# progshield.net
KiCad netlist of a schematic drawn in EAGLE
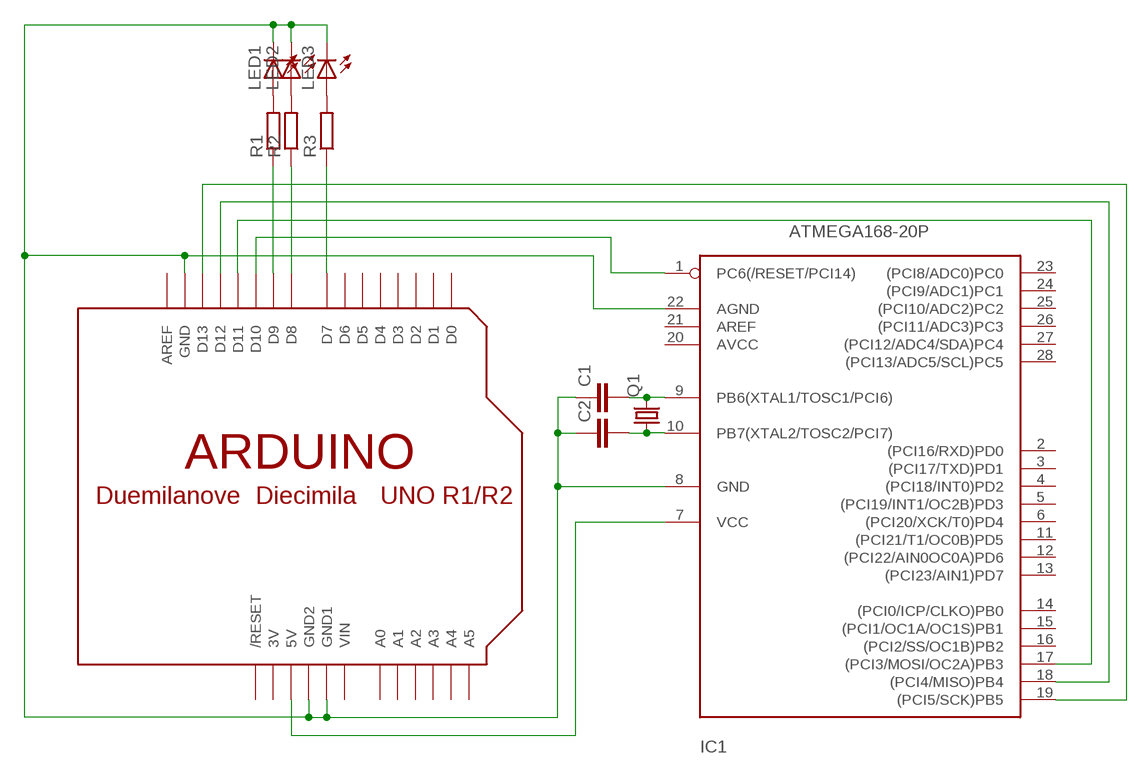
[diagram p0: schematic, sheet 1]

(export (version "E")
  (design (tool "Eeschema 10.0.6"))
  (components
    (comp (ref "C1")
      (value "C-EU025-030X050")
      (footprint "eagle-import:C025-030X050")
      (libsource (lib "eagle-import") (part "C-EU025-030X050"))
    )
    (comp (ref "C2")
      (value "C-EU025-030X050")
      (footprint "eagle-import:C025-030X050")
      (libsource (lib "eagle-import") (part "C-EU025-030X050"))
    )
    (comp (ref "IC1")
      (value "ATMEGA168-20P")
      (footprint "eagle-import:DIL28-3")
      (libsource (lib "eagle-import") (part "ATMEGA168P-20"))
    )
    (comp (ref "LED1")
      (value "LED3MM")
      (footprint "eagle-import:LED3MM")
      (libsource (lib "eagle-import") (part "LED3MM"))
    )
    (comp (ref "LED2")
      (value "LED3MM")
      (footprint "eagle-import:LED3MM")
      (libsource (lib "eagle-import") (part "LED3MM"))
    )
    (comp (ref "LED3")
      (value "LED3MM")
      (footprint "eagle-import:LED3MM")
      (libsource (lib "eagle-import") (part "LED3MM"))
    )
    (comp (ref "Q1")
      (value "CRYSTALHC49S")
      (footprint "eagle-import:HC49_S")
      (libsource (lib "eagle-import") (part "CRYSTALHC49S"))
    )
    (comp (ref "R1")
      (value "R-EU_0204/7")
      (footprint "eagle-import:0204_7")
      (libsource (lib "eagle-import") (part "R-EU_0204/7"))
    )
    (comp (ref "R2")
      (value "R-EU_0204/7")
      (footprint "eagle-import:0204_7")
      (libsource (lib "eagle-import") (part "R-EU_0204/7"))
    )
    (comp (ref "R3")
      (value "R-EU_0204/7")
      (footprint "eagle-import:0204_7")
      (libsource (lib "eagle-import") (part "R-EU_0204/7"))
    )
    (comp (ref "U$1")
      (value "ARDUINOUNO")
      (footprint "eagle-import:ARDUINO")
      (libsource (lib "eagle-import") (part "ARDUINOUNO"))
    )
  )
  (nets
    (net (code "1") (name "/3V") (class "Default")
      (node (ref "U$1") (pin "3V") (pinfunction "3V_3V") (pintype "power_in"))
    )
    (net (code "2") (name "/VIN") (class "Default")
      (node (ref "U$1") (pin "VIN") (pinfunction "VIN_VIN") (pintype "power_in"))
    )
    (net (code "3") (name "Net-(IC1-(PCI3{slash}MOSI{slash}OC2A)PB3)") (class "Default")
      (node (ref "IC1") (pin "17") (pinfunction "(PCI3/MOSI/OC2A)PB3_17") (pintype "bidirectional"))
      (node (ref "U$1") (pin "D11") (pinfunction "D11_D11") (pintype "bidirectional"))
    )
    (net (code "4") (name "Net-(IC1-(PCI4{slash}MISO)PB4)") (class "Default")
      (node (ref "IC1") (pin "18") (pinfunction "(PCI4/MISO)PB4_18") (pintype "bidirectional"))
      (node (ref "U$1") (pin "D12") (pinfunction "D12_D12") (pintype "bidirectional"))
    )
    (net (code "5") (name "Net-(IC1-(PCI5{slash}SCK)PB5)") (class "Default")
      (node (ref "IC1") (pin "19") (pinfunction "(PCI5/SCK)PB5_19") (pintype "bidirectional"))
      (node (ref "U$1") (pin "D13") (pinfunction "D13_D13") (pintype "bidirectional"))
    )
    (net (code "6") (name "Net-(IC1-AGND)") (class "Default")
      (node (ref "C1") (pin "1") (pinfunction "1_1") (pintype "passive"))
      (node (ref "C2") (pin "1") (pinfunction "1_1") (pintype "passive"))
      (node (ref "IC1") (pin "22") (pinfunction "AGND_22") (pintype "bidirectional"))
      (node (ref "IC1") (pin "8") (pinfunction "GND_8") (pintype "bidirectional"))
      (node (ref "LED1") (pin "K") (pinfunction "C_K") (pintype "passive"))
      (node (ref "LED2") (pin "K") (pinfunction "C_K") (pintype "passive"))
      (node (ref "LED3") (pin "K") (pinfunction "C_K") (pintype "passive"))
      (node (ref "U$1") (pin "GND") (pinfunction "GND_GND") (pintype "power_in"))
      (node (ref "U$1") (pin "GND1") (pinfunction "GND1_GND1") (pintype "power_in"))
      (node (ref "U$1") (pin "GND2") (pinfunction "GND2_GND2") (pintype "power_in"))
    )
    (net (code "7") (name "Net-(IC1-PB6(XTAL1{slash}TOSC1{slash}PCI6))") (class "Default")
      (node (ref "C1") (pin "2") (pinfunction "2_2") (pintype "passive"))
      (node (ref "IC1") (pin "9") (pinfunction "PB6(XTAL1/TOSC1/PCI6)_9") (pintype "bidirectional"))
      (node (ref "Q1") (pin "2") (pinfunction "2_2") (pintype "passive"))
    )
    (net (code "8") (name "Net-(IC1-PB7(XTAL2{slash}TOSC2{slash}PCI7))") (class "Default")
      (node (ref "C2") (pin "2") (pinfunction "2_2") (pintype "passive"))
      (node (ref "IC1") (pin "10") (pinfunction "PB7(XTAL2/TOSC2/PCI7)_10") (pintype "bidirectional"))
      (node (ref "Q1") (pin "1") (pinfunction "1_1") (pintype "passive"))
    )
    (net (code "9") (name "Net-(IC1-PC6({slash}RESET{slash}PCI14))") (class "Default")
      (node (ref "IC1") (pin "1") (pinfunction "PC6(/RESET/PCI14)_1") (pintype "bidirectional"))
      (node (ref "U$1") (pin "D10") (pinfunction "D10_D10") (pintype "bidirectional"))
    )
    (net (code "10") (name "Net-(IC1-VCC)") (class "Default")
      (node (ref "IC1") (pin "7") (pinfunction "VCC_7") (pintype "bidirectional"))
      (node (ref "U$1") (pin "5V") (pinfunction "5V_5V") (pintype "power_in"))
    )
    (net (code "11") (name "Net-(LED1-PadA)") (class "Default")
      (node (ref "LED1") (pin "A") (pinfunction "A_A") (pintype "passive"))
      (node (ref "R1") (pin "2") (pinfunction "2_2") (pintype "passive"))
    )
    (net (code "12") (name "Net-(LED2-PadA)") (class "Default")
      (node (ref "LED2") (pin "A") (pinfunction "A_A") (pintype "passive"))
      (node (ref "R2") (pin "2") (pinfunction "2_2") (pintype "passive"))
    )
    (net (code "13") (name "Net-(LED3-PadA)") (class "Default")
      (node (ref "LED3") (pin "A") (pinfunction "A_A") (pintype "passive"))
      (node (ref "R3") (pin "2") (pinfunction "2_2") (pintype "passive"))
    )
    (net (code "14") (name "Net-(R1-Pad1)") (class "Default")
      (node (ref "R1") (pin "1") (pinfunction "1_1") (pintype "passive"))
      (node (ref "U$1") (pin "D9") (pinfunction "D9_D9") (pintype "bidirectional"))
    )
    (net (code "15") (name "Net-(R2-Pad1)") (class "Default")
      (node (ref "R2") (pin "1") (pinfunction "1_1") (pintype "passive"))
      (node (ref "U$1") (pin "D8") (pinfunction "D8_D8") (pintype "bidirectional"))
    )
    (net (code "16") (name "Net-(R3-Pad1)") (class "Default")
      (node (ref "R3") (pin "1") (pinfunction "1_1") (pintype "passive"))
      (node (ref "U$1") (pin "D7") (pinfunction "D7_D7") (pintype "bidirectional"))
    )
    (net (code "17") (name "unconnected-(IC1-(PCI0{slash}ICP{slash}CLKO)PB0-Pad14)") (class "Default")
      (node (ref "IC1") (pin "14") (pinfunction "(PCI0/ICP/CLKO)PB0_14") (pintype "bidirectional"))
    )
    (net (code "18") (name "unconnected-(IC1-(PCI1{slash}OC1A{slash}OC1S)PB1-Pad15)") (class "Default")
      (node (ref "IC1") (pin "15") (pinfunction "(PCI1/OC1A/OC1S)PB1_15") (pintype "bidirectional"))
    )
    (net (code "19") (name "unconnected-(IC1-(PCI2{slash}SS{slash}OC1B)PB2-Pad16)") (class "Default")
      (node (ref "IC1") (pin "16") (pinfunction "(PCI2/SS/OC1B)PB2_16") (pintype "bidirectional"))
    )
    (net (code "20") (name "unconnected-(IC1-(PCI8{slash}ADC0)PC0-Pad23)") (class "Default")
      (node (ref "IC1") (pin "23") (pinfunction "(PCI8/ADC0)PC0_23") (pintype "bidirectional"))
    )
    (net (code "21") (name "unconnected-(IC1-(PCI9{slash}ADC1)PC1-Pad24)") (class "Default")
      (node (ref "IC1") (pin "24") (pinfunction "(PCI9/ADC1)PC1_24") (pintype "bidirectional"))
    )
    (net (code "22") (name "unconnected-(IC1-(PCI10{slash}ADC2)PC2-Pad25)") (class "Default")
      (node (ref "IC1") (pin "25") (pinfunction "(PCI10/ADC2)PC2_25") (pintype "bidirectional"))
    )
    (net (code "23") (name "unconnected-(IC1-(PCI11{slash}ADC3)PC3-Pad26)") (class "Default")
      (node (ref "IC1") (pin "26") (pinfunction "(PCI11/ADC3)PC3_26") (pintype "bidirectional"))
    )
    (net (code "24") (name "unconnected-(IC1-(PCI12{slash}ADC4{slash}SDA)PC4-Pad27)") (class "Default")
      (node (ref "IC1") (pin "27") (pinfunction "(PCI12/ADC4/SDA)PC4_27") (pintype "bidirectional"))
    )
    (net (code "25") (name "unconnected-(IC1-(PCI13{slash}ADC5{slash}SCL)PC5-Pad28)") (class "Default")
      (node (ref "IC1") (pin "28") (pinfunction "(PCI13/ADC5/SCL)PC5_28") (pintype "bidirectional"))
    )
    (net (code "26") (name "unconnected-(IC1-(PCI16{slash}RXD)PD0-Pad2)") (class "Default")
      (node (ref "IC1") (pin "2") (pinfunction "(PCI16/RXD)PD0_2") (pintype "bidirectional"))
    )
    (net (code "27") (name "unconnected-(IC1-(PCI17{slash}TXD)PD1-Pad3)") (class "Default")
      (node (ref "IC1") (pin "3") (pinfunction "(PCI17/TXD)PD1_3") (pintype "bidirectional"))
    )
    (net (code "28") (name "unconnected-(IC1-(PCI18{slash}INT0)PD2-Pad4)") (class "Default")
      (node (ref "IC1") (pin "4") (pinfunction "(PCI18/INT0)PD2_4") (pintype "bidirectional"))
    )
    (net (code "29") (name "unconnected-(IC1-(PCI19{slash}INT1{slash}OC2B)PD3-Pad5)") (class "Default")
      (node (ref "IC1") (pin "5") (pinfunction "(PCI19/INT1/OC2B)PD3_5") (pintype "bidirectional"))
    )
    (net (code "30") (name "unconnected-(IC1-(PCI20{slash}XCK{slash}T0)PD4-Pad6)") (class "Default")
      (node (ref "IC1") (pin "6") (pinfunction "(PCI20/XCK/T0)PD4_6") (pintype "bidirectional"))
    )
    (net (code "31") (name "unconnected-(IC1-(PCI21{slash}T1{slash}OC0B)PD5-Pad11)") (class "Default")
      (node (ref "IC1") (pin "11") (pinfunction "(PCI21/T1/OC0B)PD5_11") (pintype "bidirectional"))
    )
    (net (code "32") (name "unconnected-(IC1-(PCI22{slash}AIN0OC0A)PD6-Pad12)") (class "Default")
      (node (ref "IC1") (pin "12") (pinfunction "(PCI22/AIN0OC0A)PD6_12") (pintype "bidirectional"))
    )
    (net (code "33") (name "unconnected-(IC1-(PCI23{slash}AIN1)PD7-Pad13)") (class "Default")
      (node (ref "IC1") (pin "13") (pinfunction "(PCI23/AIN1)PD7_13") (pintype "bidirectional"))
    )
    (net (code "34") (name "unconnected-(IC1-AREF-Pad21)") (class "Default")
      (node (ref "IC1") (pin "21") (pinfunction "AREF_21") (pintype "bidirectional"))
    )
    (net (code "35") (name "unconnected-(IC1-AVCC-Pad20)") (class "Default")
      (node (ref "IC1") (pin "20") (pinfunction "AVCC_20") (pintype "bidirectional"))
    )
    (net (code "36") (name "unconnected-(U$1-PadA0)") (class "Default")
      (node (ref "U$1") (pin "A0") (pinfunction "A0_A0") (pintype "bidirectional"))
    )
    (net (code "37") (name "unconnected-(U$1-PadA1)") (class "Default")
      (node (ref "U$1") (pin "A1") (pinfunction "A1_A1") (pintype "bidirectional"))
    )
    (net (code "38") (name "unconnected-(U$1-PadA2)") (class "Default")
      (node (ref "U$1") (pin "A2") (pinfunction "A2_A2") (pintype "bidirectional"))
    )
    (net (code "39") (name "unconnected-(U$1-PadA3)") (class "Default")
      (node (ref "U$1") (pin "A3") (pinfunction "A3_A3") (pintype "bidirectional"))
    )
    (net (code "40") (name "unconnected-(U$1-PadA4)") (class "Default")
      (node (ref "U$1") (pin "A4") (pinfunction "A4_A4") (pintype "bidirectional"))
    )
    (net (code "41") (name "unconnected-(U$1-PadA5)") (class "Default")
      (node (ref "U$1") (pin "A5") (pinfunction "A5_A5") (pintype "bidirectional"))
    )
    (net (code "42") (name "unconnected-(U$1-PadAREF)") (class "Default")
      (node (ref "U$1") (pin "AREF") (pinfunction "AREF_AREF") (pintype "bidirectional"))
    )
    (net (code "43") (name "unconnected-(U$1-PadD0)") (class "Default")
      (node (ref "U$1") (pin "D0") (pinfunction "D0_D0") (pintype "bidirectional"))
    )
    (net (code "44") (name "unconnected-(U$1-PadD1)") (class "Default")
      (node (ref "U$1") (pin "D1") (pinfunction "D1_D1") (pintype "bidirectional"))
    )
    (net (code "45") (name "unconnected-(U$1-PadD2)") (class "Default")
      (node (ref "U$1") (pin "D2") (pinfunction "D2_D2") (pintype "bidirectional"))
    )
    (net (code "46") (name "unconnected-(U$1-PadD3)") (class "Default")
      (node (ref "U$1") (pin "D3") (pinfunction "D3_D3") (pintype "bidirectional"))
    )
    (net (code "47") (name "unconnected-(U$1-PadD4)") (class "Default")
      (node (ref "U$1") (pin "D4") (pinfunction "D4_D4") (pintype "bidirectional"))
    )
    (net (code "48") (name "unconnected-(U$1-PadD5)") (class "Default")
      (node (ref "U$1") (pin "D5") (pinfunction "D5_D5") (pintype "bidirectional"))
    )
    (net (code "49") (name "unconnected-(U$1-PadD6)") (class "Default")
      (node (ref "U$1") (pin "D6") (pinfunction "D6_D6") (pintype "bidirectional"))
    )
    (net (code "50") (name "unconnected-(U$1-{slash}RESET-PadRESET)") (class "Default")
      (node (ref "U$1") (pin "RESET") (pinfunction "/RESET_RESET") (pintype "bidirectional"))
    )
  )
)
